# bbf-eurojacks.net
KiCad netlist of a schematic drawn in EAGLE
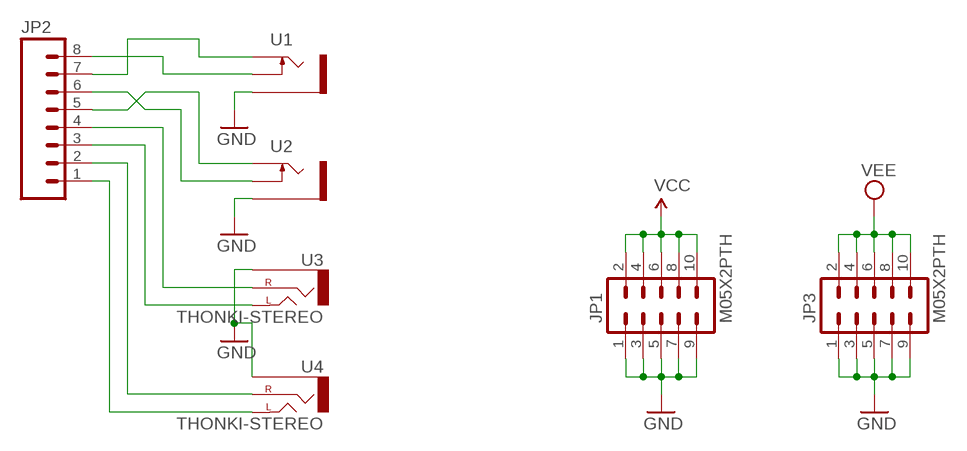
[diagram p0: schematic, sheet 1]

(export (version "E")
  (design (tool "Eeschema 10.0.6"))
  (components
    (comp (ref "JP1")
      (value "M05X2PTH")
      (footprint "eagle-import:AVR_ICSP")
      (libsource (lib "eagle-import") (part "M05X2PTH"))
    )
    (comp (ref "JP2")
      (value "M08")
      (footprint "eagle-import:1X08")
      (libsource (lib "eagle-import") (part "M08"))
    )
    (comp (ref "JP3")
      (value "M05X2PTH")
      (footprint "eagle-import:AVR_ICSP")
      (libsource (lib "eagle-import") (part "M05X2PTH"))
    )
    (comp (ref "U1")
      (value "THONKICONNNEW")
      (footprint "eagle-import:WQP-PJ301M-12_JACK")
      (libsource (lib "eagle-import") (part "THONKICONNNEW"))
    )
    (comp (ref "U2")
      (value "THONKICONNNEW")
      (footprint "eagle-import:WQP-PJ301M-12_JACK")
      (libsource (lib "eagle-import") (part "THONKICONNNEW"))
    )
    (comp (ref "U3")
      (value "THONKI-STEREO")
      (footprint "eagle-import:WQP-PJ366ST_JACK")
      (libsource (lib "eagle-import") (part "THONKI-STEREO"))
    )
    (comp (ref "U4")
      (value "THONKI-STEREO")
      (footprint "eagle-import:WQP-PJ366ST_JACK")
      (libsource (lib "eagle-import") (part "THONKI-STEREO"))
    )
  )
  (nets
    (net (code "1") (name "GND") (class "Default")
      (node (ref "JP1") (pin "1") (pinfunction "1_1") (pintype "passive"))
      (node (ref "JP1") (pin "3") (pinfunction "3_3") (pintype "passive"))
      (node (ref "JP1") (pin "5") (pinfunction "5_5") (pintype "passive"))
      (node (ref "JP1") (pin "7") (pinfunction "7_7") (pintype "passive"))
      (node (ref "JP1") (pin "9") (pinfunction "9_9") (pintype "passive"))
      (node (ref "JP3") (pin "1") (pinfunction "1_1") (pintype "passive"))
      (node (ref "JP3") (pin "3") (pinfunction "3_3") (pintype "passive"))
      (node (ref "JP3") (pin "5") (pinfunction "5_5") (pintype "passive"))
      (node (ref "JP3") (pin "7") (pinfunction "7_7") (pintype "passive"))
      (node (ref "JP3") (pin "9") (pinfunction "9_9") (pintype "passive"))
      (node (ref "U1") (pin "P$3_SLEEVE") (pinfunction "SLEEVE_P$3_SLEEVE") (pintype "passive"))
      (node (ref "U2") (pin "P$3_SLEEVE") (pinfunction "SLEEVE_P$3_SLEEVE") (pintype "passive"))
      (node (ref "U3") (pin "P$3_SLEEVE") (pinfunction "SLEEVE_P$3_SLEEVE") (pintype "bidirectional"))
      (node (ref "U4") (pin "P$3_SLEEVE") (pinfunction "SLEEVE_P$3_SLEEVE") (pintype "bidirectional"))
    )
    (net (code "2") (name "Net-(U1-SWITCH)") (class "Default")
      (node (ref "JP2") (pin "8") (pinfunction "8_8") (pintype "passive"))
      (node (ref "U1") (pin "P$2_SWITCH") (pinfunction "SWITCH_P$2_SWITCH") (pintype "passive"))
    )
    (net (code "3") (name "Net-(U1-TIP)") (class "Default")
      (node (ref "JP2") (pin "7") (pinfunction "7_7") (pintype "passive"))
      (node (ref "U1") (pin "P$1_TIP") (pinfunction "TIP_P$1_TIP") (pintype "passive"))
    )
    (net (code "4") (name "Net-(U2-SWITCH)") (class "Default")
      (node (ref "JP2") (pin "6") (pinfunction "6_6") (pintype "passive"))
      (node (ref "U2") (pin "P$2_SWITCH") (pinfunction "SWITCH_P$2_SWITCH") (pintype "passive"))
    )
    (net (code "5") (name "Net-(U2-TIP)") (class "Default")
      (node (ref "JP2") (pin "5") (pinfunction "5_5") (pintype "passive"))
      (node (ref "U2") (pin "P$1_TIP") (pinfunction "TIP_P$1_TIP") (pintype "passive"))
    )
    (net (code "6") (name "Net-(U3-LEFT)") (class "Default")
      (node (ref "JP2") (pin "3") (pinfunction "3_3") (pintype "passive"))
      (node (ref "U3") (pin "P$1_TIP") (pinfunction "LEFT_P$1_TIP") (pintype "bidirectional"))
    )
    (net (code "7") (name "Net-(U3-RIGHT)") (class "Default")
      (node (ref "JP2") (pin "4") (pinfunction "4_4") (pintype "passive"))
      (node (ref "U3") (pin "P$2_SWITCH") (pinfunction "RIGHT_P$2_SWITCH") (pintype "bidirectional"))
    )
    (net (code "8") (name "Net-(U4-LEFT)") (class "Default")
      (node (ref "JP2") (pin "1") (pinfunction "1_1") (pintype "passive"))
      (node (ref "U4") (pin "P$1_TIP") (pinfunction "LEFT_P$1_TIP") (pintype "bidirectional"))
    )
    (net (code "9") (name "Net-(U4-RIGHT)") (class "Default")
      (node (ref "JP2") (pin "2") (pinfunction "2_2") (pintype "passive"))
      (node (ref "U4") (pin "P$2_SWITCH") (pinfunction "RIGHT_P$2_SWITCH") (pintype "bidirectional"))
    )
    (net (code "10") (name "VCC") (class "Default")
      (node (ref "JP1") (pin "10") (pinfunction "10_10") (pintype "passive"))
      (node (ref "JP1") (pin "2") (pinfunction "2_2") (pintype "passive"))
      (node (ref "JP1") (pin "4") (pinfunction "4_4") (pintype "passive"))
      (node (ref "JP1") (pin "6") (pinfunction "6_6") (pintype "passive"))
      (node (ref "JP1") (pin "8") (pinfunction "8_8") (pintype "passive"))
    )
    (net (code "11") (name "VEE") (class "Default")
      (node (ref "JP3") (pin "10") (pinfunction "10_10") (pintype "passive"))
      (node (ref "JP3") (pin "2") (pinfunction "2_2") (pintype "passive"))
      (node (ref "JP3") (pin "4") (pinfunction "4_4") (pintype "passive"))
      (node (ref "JP3") (pin "6") (pinfunction "6_6") (pintype "passive"))
      (node (ref "JP3") (pin "8") (pinfunction "8_8") (pintype "passive"))
    )
  )
)
